# Inverter_Half_H-Bridge_20A_50khz.net
KiCad netlist of a schematic drawn in EAGLE
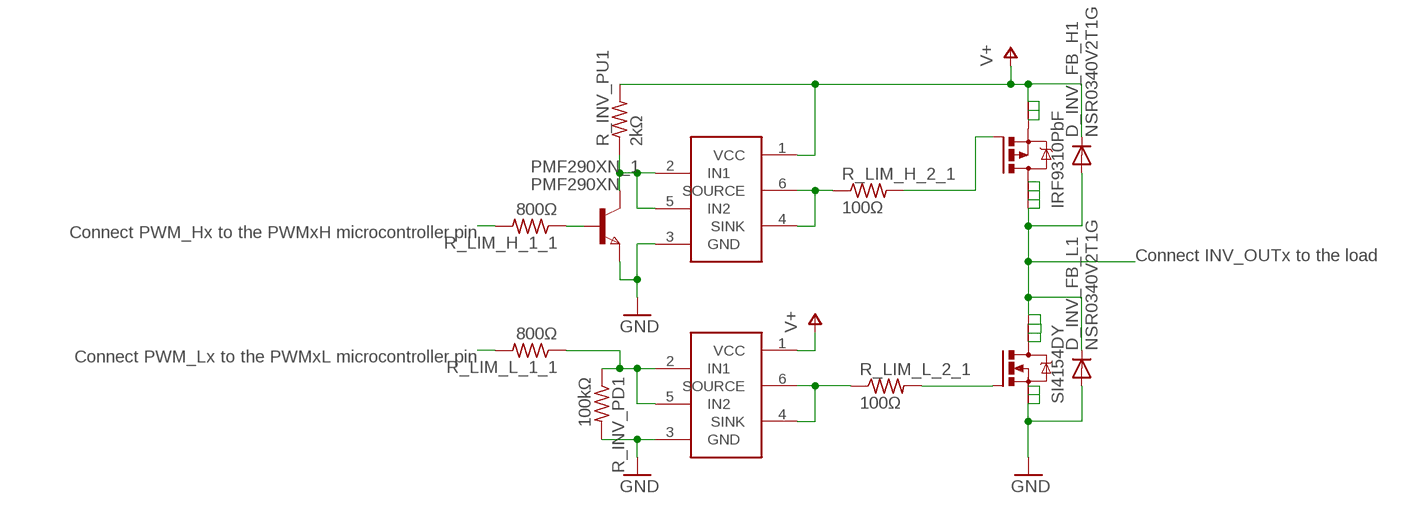
[diagram p0: schematic, sheet 1]

(export (version "E")
  (design (tool "Eeschema 10.0.6"))
  (components
    (comp (ref "D_INV_FB_H1")
      (value "NSR0340V2T1G")
      (footprint "eagle-import:SOD523")
      (libsource (lib "eagle-import") (part "DIODE-SOD523"))
    )
    (comp (ref "D_INV_FB_L1")
      (value "NSR0340V2T1G")
      (footprint "eagle-import:SOD523")
      (libsource (lib "eagle-import") (part "DIODE-SOD523"))
    )
    (comp (ref "IRF9310PBF_1")
      (value "IRF9310PbF")
      (footprint "eagle-import:SO-08")
      (libsource (lib "eagle-import") (part "P-MOSFET-SO8"))
    )
    (comp (ref "PMF290XN_1")
      (value "PMF290XN")
      (footprint "eagle-import:SOT323")
      (libsource (lib "eagle-import") (part "NPNSOT323"))
    )
    (comp (ref "R_INV_PD1")
      (value "100kΩ")
      (footprint "eagle-import:R0603")
      (fields (field (name "PART#") "RNCP0603FTD825RCT-ND"))
      (libsource (lib "eagle-import") (part "R-US_R0603"))
    )
    (comp (ref "R_INV_PU1")
      (value "2kΩ")
      (footprint "eagle-import:R0603")
      (libsource (lib "eagle-import") (part "R-US_R0603"))
    )
    (comp (ref "R_LIM_H_1_1")
      (value "800Ω")
      (footprint "eagle-import:R0603")
      (libsource (lib "eagle-import") (part "R-US_R0603"))
    )
    (comp (ref "R_LIM_H_2_1")
      (value "100Ω")
      (footprint "eagle-import:R0603")
      (libsource (lib "eagle-import") (part "R-US_R0603"))
    )
    (comp (ref "R_LIM_L_1_1")
      (value "800Ω")
      (footprint "eagle-import:R0603")
      (libsource (lib "eagle-import") (part "R-US_R0603"))
    )
    (comp (ref "R_LIM_L_2_1")
      (value "100Ω")
      (footprint "eagle-import:R0603")
      (libsource (lib "eagle-import") (part "R-US_R0603"))
    )
    (comp (ref "SI4154DY_1")
      (value "SI4154DY")
      (footprint "eagle-import:SO-08")
      (libsource (lib "eagle-import") (part "N-MOSFET-SO8S"))
    )
    (comp (ref "ZXGD3004E6_H_1")
      (value "ZXGD3004E6")
      (footprint "eagle-import:SOT23-6")
      (libsource (lib "eagle-import") (part "ZXGD3004E6"))
    )
    (comp (ref "ZXGD3004E6_L_1")
      (value "ZXGD3004E6")
      (footprint "eagle-import:SOT23-6")
      (libsource (lib "eagle-import") (part "ZXGD3004E6"))
    )
  )
  (nets
    (net (code "1") (name "GND") (class "Default")
      (node (ref "D_INV_FB_L1") (pin "A") (pinfunction "A_A") (pintype "passive"))
      (node (ref "PMF290XN_1") (pin "3") (pinfunction "E_3") (pintype "passive"))
      (node (ref "R_INV_PD1") (pin "2") (pinfunction "2_2") (pintype "passive"))
      (node (ref "SI4154DY_1") (pin "1") (pinfunction "S_1") (pintype "passive"))
      (node (ref "SI4154DY_1") (pin "2") (pinfunction "S_2") (pintype "passive"))
      (node (ref "SI4154DY_1") (pin "3") (pinfunction "S_3") (pintype "passive"))
      (node (ref "ZXGD3004E6_H_1") (pin "3") (pinfunction "GND_3") (pintype "power_in"))
      (node (ref "ZXGD3004E6_L_1") (pin "3") (pinfunction "GND_3") (pintype "power_in"))
    )
    (net (code "2") (name "Net-(D_INV_FB_H1-PadA)") (class "Default")
      (node (ref "D_INV_FB_H1") (pin "A") (pinfunction "A_A") (pintype "passive"))
      (node (ref "D_INV_FB_L1") (pin "C") (pinfunction "C_C") (pintype "passive"))
      (node (ref "IRF9310PBF_1") (pin "5") (pinfunction "D_5") (pintype "passive"))
      (node (ref "IRF9310PBF_1") (pin "6") (pinfunction "D_6") (pintype "passive"))
      (node (ref "IRF9310PBF_1") (pin "7") (pinfunction "D_7") (pintype "passive"))
      (node (ref "IRF9310PBF_1") (pin "8") (pinfunction "D_8") (pintype "passive"))
      (node (ref "SI4154DY_1") (pin "5") (pinfunction "D_5") (pintype "passive"))
      (node (ref "SI4154DY_1") (pin "6") (pinfunction "D_6") (pintype "passive"))
      (node (ref "SI4154DY_1") (pin "7") (pinfunction "D_7") (pintype "passive"))
      (node (ref "SI4154DY_1") (pin "8") (pinfunction "D_8") (pintype "passive"))
    )
    (net (code "3") (name "Net-(IRF9310PBF_1-G)") (class "Default")
      (node (ref "IRF9310PBF_1") (pin "4") (pinfunction "G_4") (pintype "passive"))
      (node (ref "R_LIM_H_2_1") (pin "2") (pinfunction "2_2") (pintype "passive"))
    )
    (net (code "4") (name "Net-(PMF290XN_1-B)") (class "Default")
      (node (ref "PMF290XN_1") (pin "2") (pinfunction "B_2") (pintype "passive"))
      (node (ref "R_LIM_H_1_1") (pin "1") (pinfunction "1_1") (pintype "passive"))
    )
    (net (code "5") (name "Net-(PMF290XN_1-C)") (class "Default")
      (node (ref "PMF290XN_1") (pin "1") (pinfunction "C_1") (pintype "passive"))
      (node (ref "R_INV_PU1") (pin "1") (pinfunction "1_1") (pintype "passive"))
      (node (ref "ZXGD3004E6_H_1") (pin "2") (pinfunction "IN1_2") (pintype "input"))
      (node (ref "ZXGD3004E6_H_1") (pin "5") (pinfunction "IN2_5") (pintype "input"))
    )
    (net (code "6") (name "Net-(SI4154DY_1-G)") (class "Default")
      (node (ref "R_LIM_L_2_1") (pin "2") (pinfunction "2_2") (pintype "passive"))
      (node (ref "SI4154DY_1") (pin "4") (pinfunction "G_4") (pintype "passive"))
    )
    (net (code "7") (name "Net-(ZXGD3004E6_H_1-SINK)") (class "Default")
      (node (ref "R_LIM_H_2_1") (pin "1") (pinfunction "1_1") (pintype "passive"))
      (node (ref "ZXGD3004E6_H_1") (pin "4") (pinfunction "SINK_4") (pintype "output"))
      (node (ref "ZXGD3004E6_H_1") (pin "6") (pinfunction "SOURCE_6") (pintype "output"))
    )
    (net (code "8") (name "Net-(ZXGD3004E6_L_1-IN1)") (class "Default")
      (node (ref "R_INV_PD1") (pin "1") (pinfunction "1_1") (pintype "passive"))
      (node (ref "R_LIM_L_1_1") (pin "1") (pinfunction "1_1") (pintype "passive"))
      (node (ref "ZXGD3004E6_L_1") (pin "2") (pinfunction "IN1_2") (pintype "input"))
      (node (ref "ZXGD3004E6_L_1") (pin "5") (pinfunction "IN2_5") (pintype "input"))
    )
    (net (code "9") (name "Net-(ZXGD3004E6_L_1-SINK)") (class "Default")
      (node (ref "R_LIM_L_2_1") (pin "1") (pinfunction "1_1") (pintype "passive"))
      (node (ref "ZXGD3004E6_L_1") (pin "4") (pinfunction "SINK_4") (pintype "output"))
      (node (ref "ZXGD3004E6_L_1") (pin "6") (pinfunction "SOURCE_6") (pintype "output"))
    )
    (net (code "10") (name "V+") (class "Default")
      (node (ref "D_INV_FB_H1") (pin "C") (pinfunction "C_C") (pintype "passive"))
      (node (ref "IRF9310PBF_1") (pin "1") (pinfunction "S_1") (pintype "passive"))
      (node (ref "IRF9310PBF_1") (pin "2") (pinfunction "S_2") (pintype "passive"))
      (node (ref "IRF9310PBF_1") (pin "3") (pinfunction "S_3") (pintype "passive"))
      (node (ref "R_INV_PU1") (pin "2") (pinfunction "2_2") (pintype "passive"))
      (node (ref "ZXGD3004E6_H_1") (pin "1") (pinfunction "VCC_1") (pintype "power_in"))
      (node (ref "ZXGD3004E6_L_1") (pin "1") (pinfunction "VCC_1") (pintype "power_in"))
    )
    (net (code "11") (name "unconnected-(R_LIM_H_1_1-Pad2)") (class "Default")
      (node (ref "R_LIM_H_1_1") (pin "2") (pinfunction "2_2") (pintype "passive"))
    )
    (net (code "12") (name "unconnected-(R_LIM_L_1_1-Pad2)") (class "Default")
      (node (ref "R_LIM_L_1_1") (pin "2") (pinfunction "2_2") (pintype "passive"))
    )
  )
)
